# shinobi_pwm.net
KiCad netlist of a schematic drawn in EAGLE
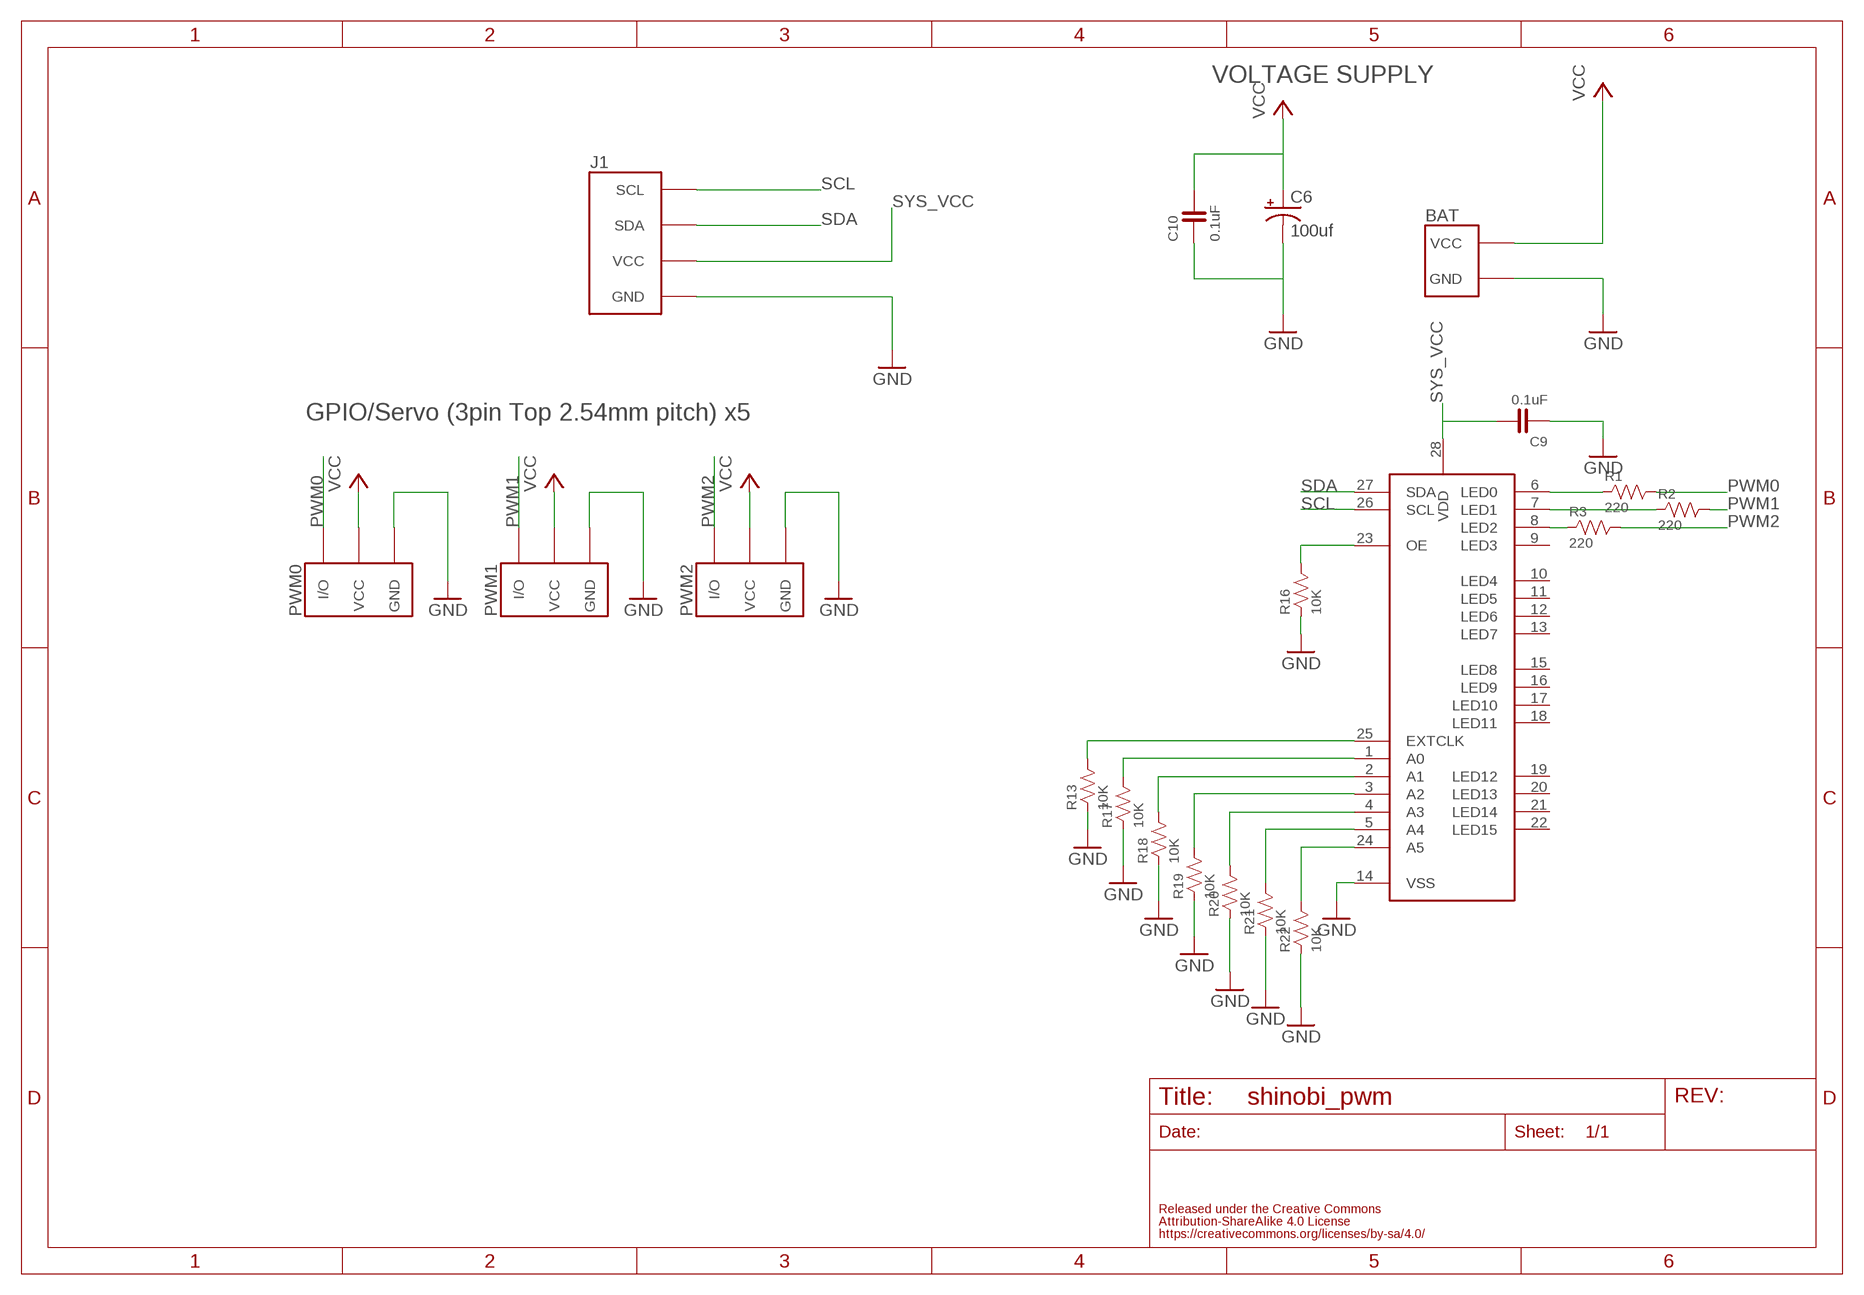
[diagram p0: schematic, sheet 1]

(export (version "E")
  (design (tool "Eeschema 10.0.6"))
  (components
    (comp (ref "BAT")
      (value "FABO_BRICK_2PIN_SIDE")
      (footprint "eagle-import:FABO_BRICK_2PIN_S02B−PASK-2_SILK")
      (libsource (lib "eagle-import") (part "FABO_BRICK_2PIN_SIDE"))
    )
    (comp (ref "C6")
      (value "100uf")
      (footprint "eagle-import:153CLV-0405")
      (libsource (lib "eagle-import") (part "CPOL-US153CLV-0405"))
    )
    (comp (ref "C9")
      (value "0.1uF")
      (footprint "eagle-import:0603")
      (libsource (lib "eagle-import") (part "CAPACITOR-0603"))
    )
    (comp (ref "C10")
      (value "0.1uF")
      (footprint "eagle-import:0603")
      (libsource (lib "eagle-import") (part "CAPACITOR-0603"))
    )
    (comp (ref "J1")
      (value "FABO_BRICK_I2C-S04B-PASK-2_LONG")
      (footprint "eagle-import:FABO_BRICK_I2C_S04B-PASK-2_LONG")
      (libsource (lib "eagle-import") (part "FABO_BRICK_I2C-S04B-PASK-2_LONG"))
    )
    (comp (ref "PWM0")
      (value "FABO_BRICK_3PIN-HEADER")
      (footprint "eagle-import:FABO_BRICK_3PIN_HEADER")
      (libsource (lib "eagle-import") (part "FABO_BRICK_3PIN-HEADER"))
    )
    (comp (ref "PWM1")
      (value "FABO_BRICK_3PIN-HEADER")
      (footprint "eagle-import:FABO_BRICK_3PIN_HEADER")
      (libsource (lib "eagle-import") (part "FABO_BRICK_3PIN-HEADER"))
    )
    (comp (ref "PWM2")
      (value "FABO_BRICK_3PIN-HEADER")
      (footprint "eagle-import:FABO_BRICK_3PIN_HEADER")
      (libsource (lib "eagle-import") (part "FABO_BRICK_3PIN-HEADER"))
    )
    (comp (ref "R1")
      (value "220")
      (footprint "eagle-import:0603")
      (libsource (lib "eagle-import") (part "RESISTOR-0603"))
    )
    (comp (ref "R2")
      (value "220")
      (footprint "eagle-import:0603")
      (libsource (lib "eagle-import") (part "RESISTOR-0603"))
    )
    (comp (ref "R3")
      (value "220")
      (footprint "eagle-import:0603")
      (libsource (lib "eagle-import") (part "RESISTOR-0603"))
    )
    (comp (ref "R13")
      (value "10K")
      (footprint "eagle-import:0402")
      (libsource (lib "eagle-import") (part "RESISTOR-0402"))
    )
    (comp (ref "R16")
      (value "10K")
      (footprint "eagle-import:0603")
      (libsource (lib "eagle-import") (part "RESISTOR-0603"))
    )
    (comp (ref "R17")
      (value "10K")
      (footprint "eagle-import:0603")
      (libsource (lib "eagle-import") (part "RESISTOR-0603"))
    )
    (comp (ref "R18")
      (value "10K")
      (footprint "eagle-import:0603")
      (libsource (lib "eagle-import") (part "RESISTOR-0603"))
    )
    (comp (ref "R19")
      (value "10K")
      (footprint "eagle-import:0603")
      (libsource (lib "eagle-import") (part "RESISTOR-0603"))
    )
    (comp (ref "R20")
      (value "10K")
      (footprint "eagle-import:0603")
      (libsource (lib "eagle-import") (part "RESISTOR-0603"))
    )
    (comp (ref "R21")
      (value "10K")
      (footprint "eagle-import:0603")
      (libsource (lib "eagle-import") (part "RESISTOR-0603"))
    )
    (comp (ref "R22")
      (value "10K")
      (footprint "eagle-import:0402")
      (libsource (lib "eagle-import") (part "RESISTOR-0402"))
    )
    (comp (ref "U$9")
      (value "PCA9685")
      (footprint "eagle-import:PCA9685")
      (libsource (lib "eagle-import") (part "PCA9685"))
    )
  )
  (nets
    (net (code "1") (name "/PWM0") (class "Default")
      (node (ref "PWM0") (pin "I/O") (pinfunction "I/O_I/O") (pintype "bidirectional"))
      (node (ref "R1") (pin "2") (pinfunction "2_2") (pintype "bidirectional"))
    )
    (net (code "2") (name "/PWM1") (class "Default")
      (node (ref "PWM1") (pin "I/O") (pinfunction "I/O_I/O") (pintype "bidirectional"))
      (node (ref "R2") (pin "2") (pinfunction "2_2") (pintype "bidirectional"))
    )
    (net (code "3") (name "/PWM2") (class "Default")
      (node (ref "PWM2") (pin "I/O") (pinfunction "I/O_I/O") (pintype "bidirectional"))
      (node (ref "R3") (pin "2") (pinfunction "2_2") (pintype "bidirectional"))
    )
    (net (code "4") (name "/SCL") (class "Default")
      (node (ref "J1") (pin "SCL") (pinfunction "SCL_SCL") (pintype "bidirectional"))
      (node (ref "U$9") (pin "26") (pinfunction "SCL_26") (pintype "bidirectional"))
    )
    (net (code "5") (name "/SDA") (class "Default")
      (node (ref "J1") (pin "SDA") (pinfunction "SDA_SDA") (pintype "bidirectional"))
      (node (ref "U$9") (pin "27") (pinfunction "SDA_27") (pintype "bidirectional"))
    )
    (net (code "6") (name "/SYS_VCC") (class "Default")
      (node (ref "C9") (pin "2") (pinfunction "2_2") (pintype "passive"))
      (node (ref "J1") (pin "VCC") (pinfunction "VCC_VCC") (pintype "bidirectional"))
      (node (ref "U$9") (pin "28") (pinfunction "VDD_28") (pintype "bidirectional"))
    )
    (net (code "7") (name "GND") (class "Default")
      (node (ref "BAT") (pin "GND") (pinfunction "GND_GND") (pintype "bidirectional"))
      (node (ref "C10") (pin "1") (pinfunction "1_1") (pintype "passive"))
      (node (ref "C6") (pin "-") (pinfunction "-_-") (pintype "passive"))
      (node (ref "C9") (pin "1") (pinfunction "1_1") (pintype "passive"))
      (node (ref "J1") (pin "GND") (pinfunction "GND_GND") (pintype "bidirectional"))
      (node (ref "PWM0") (pin "GND") (pinfunction "GND_GND") (pintype "bidirectional"))
      (node (ref "PWM1") (pin "GND") (pinfunction "GND_GND") (pintype "bidirectional"))
      (node (ref "PWM2") (pin "GND") (pinfunction "GND_GND") (pintype "bidirectional"))
      (node (ref "R13") (pin "P$1") (pinfunction "1_P$1") (pintype "bidirectional"))
      (node (ref "R16") (pin "1") (pinfunction "1_1") (pintype "bidirectional"))
      (node (ref "R17") (pin "1") (pinfunction "1_1") (pintype "bidirectional"))
      (node (ref "R18") (pin "1") (pinfunction "1_1") (pintype "bidirectional"))
      (node (ref "R19") (pin "1") (pinfunction "1_1") (pintype "bidirectional"))
      (node (ref "R20") (pin "1") (pinfunction "1_1") (pintype "bidirectional"))
      (node (ref "R21") (pin "1") (pinfunction "1_1") (pintype "bidirectional"))
      (node (ref "R22") (pin "P$1") (pinfunction "1_P$1") (pintype "bidirectional"))
      (node (ref "U$9") (pin "14") (pinfunction "VSS_14") (pintype "bidirectional"))
    )
    (net (code "8") (name "Net-(R13-2)") (class "Default")
      (node (ref "R13") (pin "P$2") (pinfunction "2_P$2") (pintype "bidirectional"))
      (node (ref "U$9") (pin "25") (pinfunction "EXTCLK_25") (pintype "bidirectional"))
    )
    (net (code "9") (name "Net-(R22-2)") (class "Default")
      (node (ref "R22") (pin "P$2") (pinfunction "2_P$2") (pintype "bidirectional"))
      (node (ref "U$9") (pin "24") (pinfunction "A5_24") (pintype "bidirectional"))
    )
    (net (code "10") (name "Net-(U$9-A0)") (class "Default")
      (node (ref "R17") (pin "2") (pinfunction "2_2") (pintype "bidirectional"))
      (node (ref "U$9") (pin "1") (pinfunction "A0_1") (pintype "bidirectional"))
    )
    (net (code "11") (name "Net-(U$9-A1)") (class "Default")
      (node (ref "R18") (pin "2") (pinfunction "2_2") (pintype "bidirectional"))
      (node (ref "U$9") (pin "2") (pinfunction "A1_2") (pintype "bidirectional"))
    )
    (net (code "12") (name "Net-(U$9-A2)") (class "Default")
      (node (ref "R19") (pin "2") (pinfunction "2_2") (pintype "bidirectional"))
      (node (ref "U$9") (pin "3") (pinfunction "A2_3") (pintype "bidirectional"))
    )
    (net (code "13") (name "Net-(U$9-A3)") (class "Default")
      (node (ref "R20") (pin "2") (pinfunction "2_2") (pintype "bidirectional"))
      (node (ref "U$9") (pin "4") (pinfunction "A3_4") (pintype "bidirectional"))
    )
    (net (code "14") (name "Net-(U$9-A4)") (class "Default")
      (node (ref "R21") (pin "2") (pinfunction "2_2") (pintype "bidirectional"))
      (node (ref "U$9") (pin "5") (pinfunction "A4_5") (pintype "bidirectional"))
    )
    (net (code "15") (name "Net-(U$9-LED0)") (class "Default")
      (node (ref "R1") (pin "1") (pinfunction "1_1") (pintype "bidirectional"))
      (node (ref "U$9") (pin "6") (pinfunction "LED0_6") (pintype "bidirectional"))
    )
    (net (code "16") (name "Net-(U$9-LED1)") (class "Default")
      (node (ref "R2") (pin "1") (pinfunction "1_1") (pintype "bidirectional"))
      (node (ref "U$9") (pin "7") (pinfunction "LED1_7") (pintype "bidirectional"))
    )
    (net (code "17") (name "Net-(U$9-LED2)") (class "Default")
      (node (ref "R3") (pin "1") (pinfunction "1_1") (pintype "bidirectional"))
      (node (ref "U$9") (pin "8") (pinfunction "LED2_8") (pintype "bidirectional"))
    )
    (net (code "18") (name "Net-(U$9-OE)") (class "Default")
      (node (ref "R16") (pin "2") (pinfunction "2_2") (pintype "bidirectional"))
      (node (ref "U$9") (pin "23") (pinfunction "OE_23") (pintype "bidirectional"))
    )
    (net (code "19") (name "VCC") (class "Default")
      (node (ref "BAT") (pin "VCC") (pinfunction "VCC_VCC") (pintype "bidirectional"))
      (node (ref "C10") (pin "2") (pinfunction "2_2") (pintype "passive"))
      (node (ref "C6") (pin "+") (pinfunction "+_+") (pintype "passive"))
      (node (ref "PWM0") (pin "VCC") (pinfunction "VCC_VCC") (pintype "bidirectional"))
      (node (ref "PWM1") (pin "VCC") (pinfunction "VCC_VCC") (pintype "bidirectional"))
      (node (ref "PWM2") (pin "VCC") (pinfunction "VCC_VCC") (pintype "bidirectional"))
    )
    (net (code "20") (name "unconnected-(U$9-LED3-Pad9)") (class "Default")
      (node (ref "U$9") (pin "9") (pinfunction "LED3_9") (pintype "bidirectional"))
    )
    (net (code "21") (name "unconnected-(U$9-LED4-Pad10)") (class "Default")
      (node (ref "U$9") (pin "10") (pinfunction "LED4_10") (pintype "bidirectional"))
    )
    (net (code "22") (name "unconnected-(U$9-LED5-Pad11)") (class "Default")
      (node (ref "U$9") (pin "11") (pinfunction "LED5_11") (pintype "bidirectional"))
    )
    (net (code "23") (name "unconnected-(U$9-LED6-Pad12)") (class "Default")
      (node (ref "U$9") (pin "12") (pinfunction "LED6_12") (pintype "bidirectional"))
    )
    (net (code "24") (name "unconnected-(U$9-LED7-Pad13)") (class "Default")
      (node (ref "U$9") (pin "13") (pinfunction "LED7_13") (pintype "bidirectional"))
    )
    (net (code "25") (name "unconnected-(U$9-LED8-Pad15)") (class "Default")
      (node (ref "U$9") (pin "15") (pinfunction "LED8_15") (pintype "bidirectional"))
    )
    (net (code "26") (name "unconnected-(U$9-LED9-Pad16)") (class "Default")
      (node (ref "U$9") (pin "16") (pinfunction "LED9_16") (pintype "bidirectional"))
    )
    (net (code "27") (name "unconnected-(U$9-LED10-Pad17)") (class "Default")
      (node (ref "U$9") (pin "17") (pinfunction "LED10_17") (pintype "bidirectional"))
    )
    (net (code "28") (name "unconnected-(U$9-LED11-Pad18)") (class "Default")
      (node (ref "U$9") (pin "18") (pinfunction "LED11_18") (pintype "bidirectional"))
    )
    (net (code "29") (name "unconnected-(U$9-LED12-Pad19)") (class "Default")
      (node (ref "U$9") (pin "19") (pinfunction "LED12_19") (pintype "bidirectional"))
    )
    (net (code "30") (name "unconnected-(U$9-LED13-Pad20)") (class "Default")
      (node (ref "U$9") (pin "20") (pinfunction "LED13_20") (pintype "bidirectional"))
    )
    (net (code "31") (name "unconnected-(U$9-LED14-Pad21)") (class "Default")
      (node (ref "U$9") (pin "21") (pinfunction "LED14_21") (pintype "bidirectional"))
    )
    (net (code "32") (name "unconnected-(U$9-LED15-Pad22)") (class "Default")
      (node (ref "U$9") (pin "22") (pinfunction "LED15_22") (pintype "bidirectional"))
    )
  )
)
